# FiberOptic__3.net
KiCad netlist of a schematic drawn in Altium Designer
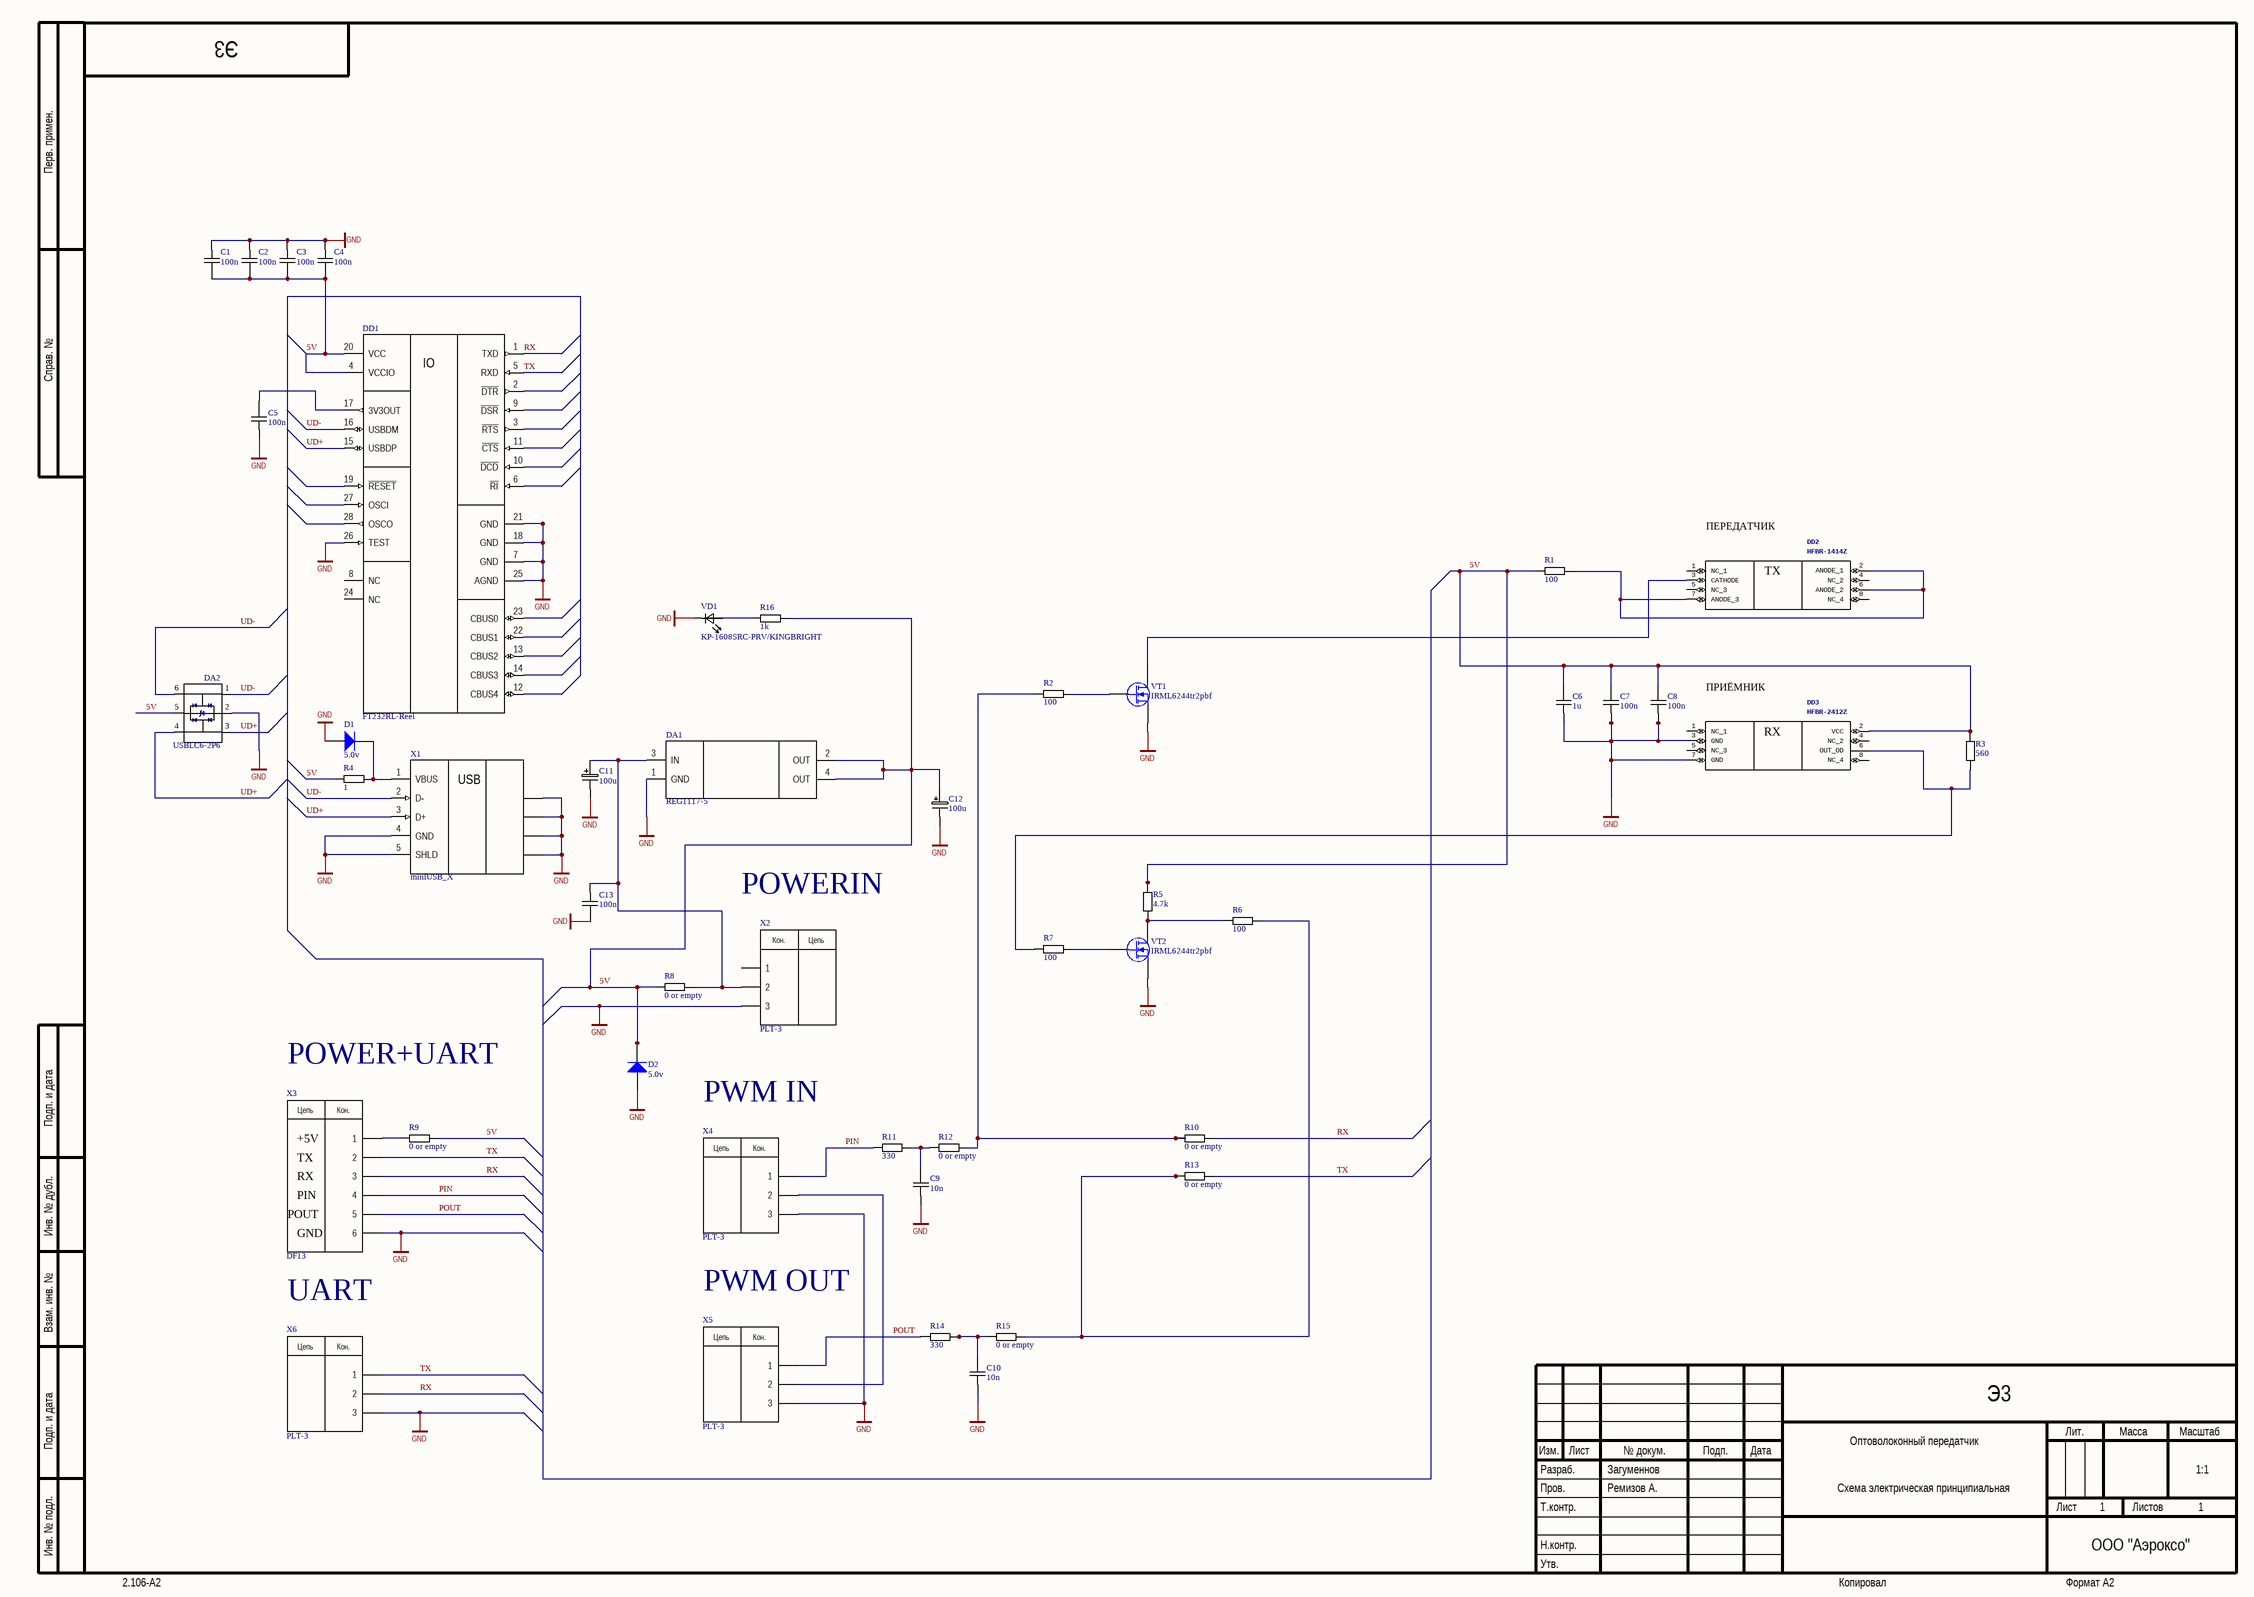
[diagram p0: FiberOptic_Э3.SchDoc]

(export (version "E")
  (design (tool "Eeschema 10.0.6"))
  (components
    (comp (ref "C1")
      (value "100n")
      (footprint "SMT0603CAP/VISHAY")
      (description "180p 50V 0603 cap")
      (libsource (lib "Логическая_Lib") (part "CC0603JRNPO9BN181/YAGEO"))
    )
    (comp (ref "C2")
      (value "100n")
      (footprint "SMT0603CAP/VISHAY")
      (description "180p 50V 0603 cap")
      (libsource (lib "Логическая_Lib") (part "CC0603JRNPO9BN181/YAGEO"))
    )
    (comp (ref "C3")
      (value "100n")
      (footprint "SMT0603CAP/VISHAY")
      (description "180p 50V 0603 cap")
      (libsource (lib "Логическая_Lib") (part "CC0603JRNPO9BN181/YAGEO"))
    )
    (comp (ref "C4")
      (value "100n")
      (footprint "SMT0603CAP/VISHAY")
      (description "180p 50V 0603 cap")
      (libsource (lib "Логическая_Lib") (part "CC0603JRNPO9BN181/YAGEO"))
    )
    (comp (ref "C5")
      (value "100n")
      (footprint "SMT0603CAP/VISHAY")
      (description "180p 50V 0603 cap")
      (libsource (lib "Логическая_Lib") (part "CC0603JRNPO9BN181/YAGEO"))
    )
    (comp (ref "C6")
      (value "1u")
      (footprint "SMT0603CAP/VISHAY")
      (description "180p 50V 0603 cap")
      (libsource (lib "Логическая_Lib") (part "CC0603JRNPO9BN181/YAGEO"))
    )
    (comp (ref "C7")
      (value "100n")
      (footprint "SMT0603CAP/VISHAY")
      (description "180p 50V 0603 cap")
      (libsource (lib "Логическая_Lib") (part "CC0603JRNPO9BN181/YAGEO"))
    )
    (comp (ref "C8")
      (value "100n")
      (footprint "SMT0603CAP/VISHAY")
      (description "180p 50V 0603 cap")
      (libsource (lib "Логическая_Lib") (part "CC0603JRNPO9BN181/YAGEO"))
    )
    (comp (ref "C9")
      (value "10n")
      (footprint "SMT0603CAP/VISHAY")
      (description "180p 50V 0603 cap")
      (libsource (lib "Логическая_Lib") (part "CC0603JRNPO9BN181/YAGEO"))
    )
    (comp (ref "C10")
      (value "10n")
      (footprint "SMT0603CAP/VISHAY")
      (description "180p 50V 0603 cap")
      (libsource (lib "Логическая_Lib") (part "CC0603JRNPO9BN181/YAGEO"))
    )
    (comp (ref "C11")
      (value "100u")
      (footprint "VISHAY-TANTALUM-CAP-TYPE-C/VISHAY")
      (description "100u 10V tantalum cap")
      (libsource (lib "FiberOptic_SCH") (part "293D107X9010C2TE3/VISHAY_1"))
    )
    (comp (ref "C12")
      (value "100u")
      (footprint "VISHAY-TANTALUM-CAP-TYPE-C/VISHAY")
      (description "100u 10V tantalum cap")
      (libsource (lib "FiberOptic_SCH") (part "293D107X9010C2TE3/VISHAY_1"))
    )
    (comp (ref "C13")
      (value "100n")
      (footprint "SMT0603CAP/VISHAY")
      (description "180p 50V 0603 cap")
      (libsource (lib "Логическая_Lib") (part "CC0603JRNPO9BN181/YAGEO"))
    )
    (comp (ref "D1")
      (value "5.0v")
      (footprint "SMB")
      (description "Default Diode")
      (fields (field (name "PUBLISHER") "Altium Limited"))
      (libsource (lib "Miscellaneous Devices") (part "Diode"))
    )
    (comp (ref "D2")
      (value "5.0v")
      (footprint "SMB")
      (description "Default Diode")
      (fields (field (name "PUBLISHER") "Altium Limited"))
      (libsource (lib "Miscellaneous Devices") (part "Diode"))
    )
    (comp (ref "DA1")
      (value "REG1117-5")
      (footprint "ZZ311")
      (description "800mA and 1A Low Dropout Positive Regulator 2.85V, 3.3V, 5V, and Adjustable")
      (fields (field (name "PUBLISHER") "Altium Limited"))
      (libsource (lib "FiberOptic_SCH") (part "REG1117-5"))
    )
    (comp (ref "DA2")
      (value "USBLC6-2P6")
      (footprint "SOT50P160X60-6N")
      (description "USBLC6 Series 2 Line 6 V SMT Bi Directional ESD Protection - SOT-666")
      (fields (field (name "MF") "STMicroelectronics"))
      (libsource (lib "FiberOptic_SCH") (part "USBLC6-2P6"))
    )
    (comp (ref "DD1")
      (value "FT232RL-Reel")
      (footprint "SSOP-28_N")
      (description "USB UART Asynchronous Serial Data Transfer Chip, 28-pin SSOP, Tape and Reel")
      (fields (field (name "MANUFACTURER") "FTDI"))
      (libsource (lib "БУГ2_Логическая_Lib") (part "FT232RL-Reel"))
    )
    (comp (ref "DD2")
      (value "HFBR-1414Z")
      (footprint "HFBR1414Z")
      (fields (field (name "RS_PART_NUMBER") "4965692"))
      (libsource (lib "FiberOptic_SCH") (part "HFBR-1414Z"))
    )
    (comp (ref "DD3")
      (value "HFBR-2412Z")
      (footprint "HFBR2412Z")
      (fields
        (field (name "MANUFACTURER_PART_NUMBER") "HFBR-1414Z")
        (field (name "RS_PART_NUMBER") "4965692")
      )
      (libsource (lib "FiberOptic_SCH") (part "HFBR-2412Z"))
    )
    (comp (ref "R1")
      (value "100")
      (footprint "SMT0603/VISHAY")
      (description "10k")
      (libsource (lib "FiberOptic_SCH") (part "CRCW060310K0FKEA/MURATA"))
    )
    (comp (ref "R2")
      (value "100")
      (footprint "SMT0603/VISHAY")
      (description "10k")
      (libsource (lib "FiberOptic_SCH") (part "CRCW060310K0FKEA/MURATA"))
    )
    (comp (ref "R3")
      (value "560")
      (footprint "SMT0603/VISHAY")
      (description "10k")
      (libsource (lib "FiberOptic_SCH") (part "CRCW060310K0FKEA/MURATA"))
    )
    (comp (ref "R4")
      (value "1")
      (footprint "SMT0603/VISHAY")
      (description "0")
      (libsource (lib "БУГ_Lib") (part "CRCW060310K0FKEA/MURATA"))
    )
    (comp (ref "R5")
      (value "4.7k")
      (footprint "SMT0603/VISHAY")
      (description "10k")
      (libsource (lib "FiberOptic_SCH") (part "CRCW060310K0FKEA/MURATA"))
    )
    (comp (ref "R6")
      (value "100")
      (footprint "SMT0603/VISHAY")
      (description "10k")
      (libsource (lib "FiberOptic_SCH") (part "CRCW060310K0FKEA/MURATA"))
    )
    (comp (ref "R7")
      (value "100")
      (footprint "SMT0603/VISHAY")
      (description "10k")
      (libsource (lib "FiberOptic_SCH") (part "CRCW060310K0FKEA/MURATA"))
    )
    (comp (ref "R8")
      (value "0 or empty")
      (footprint "SMT0603/VISHAY")
      (libsource (lib "FiberOptic_SCH") (part "CRCW060310K0FKEA/MURATA"))
    )
    (comp (ref "R9")
      (value "0 or empty")
      (footprint "SMT0603/VISHAY")
      (libsource (lib "FiberOptic_SCH") (part "CRCW060310K0FKEA/MURATA"))
    )
    (comp (ref "R10")
      (value "0 or empty")
      (footprint "SMT0603/VISHAY")
      (description "10k")
      (libsource (lib "FiberOptic_SCH") (part "CRCW060310K0FKEA/MURATA"))
    )
    (comp (ref "R11")
      (value "330")
      (footprint "SMT0603/VISHAY")
      (description "0 or empty")
      (libsource (lib "FiberOptic_SCH") (part "CRCW060310K0FKEA/MURATA"))
    )
    (comp (ref "R12")
      (value "0 or empty")
      (footprint "SMT0603/VISHAY")
      (libsource (lib "FiberOptic_SCH") (part "CRCW060310K0FKEA/MURATA"))
    )
    (comp (ref "R13")
      (value "0 or empty")
      (footprint "SMT0603/VISHAY")
      (description "10k")
      (libsource (lib "FiberOptic_SCH") (part "CRCW060310K0FKEA/MURATA"))
    )
    (comp (ref "R14")
      (value "330")
      (footprint "SMT0603/VISHAY")
      (description "10k")
      (libsource (lib "FiberOptic_SCH") (part "CRCW060310K0FKEA/MURATA"))
    )
    (comp (ref "R15")
      (value "0 or empty")
      (footprint "SMT0603/VISHAY")
      (description "10k")
      (libsource (lib "FiberOptic_SCH") (part "CRCW060310K0FKEA/MURATA"))
    )
    (comp (ref "R16")
      (value "1k")
      (footprint "SMT0603/VISHAY")
      (description "10k")
      (libsource (lib "Логическая_Lib") (part "CRCW060310K0FKEA/MURATA"))
    )
    (comp (ref "VD1")
      (value "KP-1608SRC-PRV/KINGBRIGHT")
      (footprint "1.6x0.8SMTLED/KINGBRIGHT")
      (description "Red 0603 LED")
      (libsource (lib "Логическая_Lib") (part "KP-1608SRC-PRV/KINGBRIGHT"))
    )
    (comp (ref "VT1")
      (value "IRML6244tr2pbf")
      (footprint "SOT23_N")
      (description "N-Channel MOSFET")
      (fields (field (name "PUBLISHER") "Altium Limited"))
      (libsource (lib "FiberOptic_SCH") (part "IRML6244tr2pbf"))
    )
    (comp (ref "VT2")
      (value "IRML6244tr2pbf")
      (footprint "SOT23_N")
      (description "N-Channel MOSFET")
      (fields (field (name "PUBLISHER") "Altium Limited"))
      (libsource (lib "FiberOptic_SCH") (part "IRML6244tr2pbf"))
    )
    (comp (ref "X1")
      (value "miniUSB_X")
      (footprint "miniUSB_AB")
      (description "USB 2.0, Right Angle, SMT, A Type, Receptacle, 5 Position, Black")
      (fields (field (name "PUBLISHER") "Altium Limited"))
      (libsource (lib "БУГ2_Логическая_Lib") (part "miniUSB_X"))
    )
    (comp (ref "X2") (value "PLT-3") (footprint "PLT-3T") (libsource (lib "") (part "PLT-3_1")))
    (comp (ref "X3")
      (value "DF13")
      (footprint "HIROSE DF13-6P-1.25H")
      (libsource (lib "FiberOptic_SCH") (part "DF13-6P"))
    )
    (comp (ref "X4") (value "PLT-3") (footprint "PLT-3T") (libsource (lib "FiberOptic_SCH") (part "PLT-3")))
    (comp (ref "X5") (value "PLT-3") (footprint "PLT-3T") (libsource (lib "FiberOptic_SCH") (part "PLT-3")))
    (comp (ref "X6") (value "PLT-3") (footprint "PLT-3T") (libsource (lib "FiberOptic_SCH") (part "PLT-3")))
  )
  (nets
    (net (code "1") (name "/5V") (class "Default")
      (node (ref "C1") (pin "1") (pinfunction "1_1") (pintype "passive"))
      (node (ref "C12") (pin "1") (pinfunction "1_1") (pintype "passive"))
      (node (ref "C2") (pin "1") (pinfunction "1_1") (pintype "passive"))
      (node (ref "C3") (pin "1") (pinfunction "1_1") (pintype "passive"))
      (node (ref "C4") (pin "1") (pinfunction "1_1") (pintype "passive"))
      (node (ref "C6") (pin "1") (pinfunction "1_1") (pintype "passive"))
      (node (ref "C7") (pin "1") (pinfunction "1_1") (pintype "passive"))
      (node (ref "C8") (pin "1") (pinfunction "1_1") (pintype "passive"))
      (node (ref "D2") (pin "2") (pinfunction "K_2") (pintype "passive"))
      (node (ref "DA1") (pin "2") (pinfunction "OUT_2") (pintype "power_in"))
      (node (ref "DA1") (pin "4") (pinfunction "OUT_4") (pintype "power_in"))
      (node (ref "DA2") (pin "5") (pinfunction "VBUS_5") (pintype "power_in"))
      (node (ref "DD1") (pin "20") (pinfunction "VCC_20") (pintype "power_in"))
      (node (ref "DD1") (pin "4") (pinfunction "VCCIO_4") (pintype "power_in"))
      (node (ref "DD3") (pin "2") (pinfunction "VCC_2") (pintype "bidirectional"))
      (node (ref "R1") (pin "2") (pinfunction "2_2") (pintype "passive"))
      (node (ref "R16") (pin "2") (pinfunction "2_2") (pintype "passive"))
      (node (ref "R3") (pin "2") (pinfunction "2_2") (pintype "passive"))
      (node (ref "R4") (pin "2") (pinfunction "2_2") (pintype "passive"))
      (node (ref "R5") (pin "1") (pinfunction "1_1") (pintype "passive"))
      (node (ref "R8") (pin "1") (pinfunction "1_1") (pintype "passive"))
      (node (ref "R9") (pin "2") (pinfunction "2_2") (pintype "passive"))
    )
    (net (code "2") (name "/PIN") (class "Default")
      (node (ref "R11") (pin "1") (pinfunction "1_1") (pintype "passive"))
      (node (ref "X3") (pin "4") (pinfunction "4_4") (pintype "passive"))
      (node (ref "X4") (pin "1") (pinfunction "1_1") (pintype "passive"))
    )
    (net (code "3") (name "/POUT") (class "Default")
      (node (ref "R14") (pin "1") (pinfunction "1_1") (pintype "passive"))
      (node (ref "X3") (pin "5") (pinfunction "5_5") (pintype "passive"))
      (node (ref "X5") (pin "1") (pinfunction "1_1") (pintype "passive"))
    )
    (net (code "4") (name "/RX") (class "Default")
      (node (ref "DD1") (pin "1") (pinfunction "TXD_1") (pintype "output"))
      (node (ref "R10") (pin "2") (pinfunction "2_2") (pintype "passive"))
      (node (ref "X3") (pin "3") (pinfunction "3_3") (pintype "passive"))
      (node (ref "X6") (pin "2") (pinfunction "2_2") (pintype "passive"))
    )
    (net (code "5") (name "/TX") (class "Default")
      (node (ref "DD1") (pin "5") (pinfunction "RXD_5") (pintype "input"))
      (node (ref "R13") (pin "2") (pinfunction "2_2") (pintype "passive"))
      (node (ref "X3") (pin "2") (pinfunction "2_2") (pintype "passive"))
      (node (ref "X6") (pin "1") (pinfunction "1_1") (pintype "passive"))
    )
    (net (code "6") (name "/UD+") (class "Default")
      (node (ref "DA2") (pin "3") (pinfunction "I/O2_1_3") (pintype "bidirectional"))
      (node (ref "DA2") (pin "4") (pinfunction "I/O2_2_4") (pintype "bidirectional"))
      (node (ref "DD1") (pin "15") (pinfunction "USBDP_15") (pintype "bidirectional"))
      (node (ref "X1") (pin "3") (pinfunction "D+_3") (pintype "input"))
    )
    (net (code "7") (name "/UD-") (class "Default")
      (node (ref "DA2") (pin "1") (pinfunction "I/O1_1_1") (pintype "bidirectional"))
      (node (ref "DA2") (pin "6") (pinfunction "I/O1_2_6") (pintype "bidirectional"))
      (node (ref "DD1") (pin "16") (pinfunction "USBDM_16") (pintype "bidirectional"))
      (node (ref "X1") (pin "2") (pinfunction "D-_2") (pintype "input"))
    )
    (net (code "8") (name "GND") (class "Default")
      (node (ref "C1") (pin "2") (pinfunction "2_2") (pintype "passive"))
      (node (ref "C10") (pin "2") (pinfunction "2_2") (pintype "passive"))
      (node (ref "C11") (pin "2") (pinfunction "2_2") (pintype "passive"))
      (node (ref "C12") (pin "2") (pinfunction "2_2") (pintype "passive"))
      (node (ref "C13") (pin "1") (pinfunction "1_1") (pintype "passive"))
      (node (ref "C2") (pin "2") (pinfunction "2_2") (pintype "passive"))
      (node (ref "C3") (pin "2") (pinfunction "2_2") (pintype "passive"))
      (node (ref "C4") (pin "2") (pinfunction "2_2") (pintype "passive"))
      (node (ref "C5") (pin "2") (pinfunction "2_2") (pintype "passive"))
      (node (ref "C6") (pin "2") (pinfunction "2_2") (pintype "passive"))
      (node (ref "C7") (pin "2") (pinfunction "2_2") (pintype "passive"))
      (node (ref "C8") (pin "2") (pinfunction "2_2") (pintype "passive"))
      (node (ref "C9") (pin "2") (pinfunction "2_2") (pintype "passive"))
      (node (ref "D1") (pin "1") (pinfunction "A_1") (pintype "passive"))
      (node (ref "D2") (pin "1") (pinfunction "A_1") (pintype "passive"))
      (node (ref "DA1") (pin "1") (pinfunction "GND_1") (pintype "power_in"))
      (node (ref "DA2") (pin "2") (pinfunction "GND_2") (pintype "power_in"))
      (node (ref "DD1") (pin "18") (pinfunction "GND_18") (pintype "power_in"))
      (node (ref "DD1") (pin "21") (pinfunction "GND_21") (pintype "power_in"))
      (node (ref "DD1") (pin "25") (pinfunction "AGND_25") (pintype "power_in"))
      (node (ref "DD1") (pin "26") (pinfunction "TEST_26") (pintype "input"))
      (node (ref "DD1") (pin "7") (pinfunction "GND_7") (pintype "power_in"))
      (node (ref "DD3") (pin "3") (pinfunction "GND_3") (pintype "bidirectional"))
      (node (ref "DD3") (pin "7") (pinfunction "GND_7") (pintype "bidirectional"))
      (node (ref "VD1") (pin "2") (pinfunction "2_2") (pintype "passive"))
      (node (ref "VT1") (pin "3") (pinfunction "S_3") (pintype "passive"))
      (node (ref "VT2") (pin "3") (pinfunction "S_3") (pintype "passive"))
      (node (ref "X1") (pin "4") (pinfunction "GND_4") (pintype "power_in"))
      (node (ref "X1") (pin "5") (pinfunction "SHLD_5") (pintype "passive"))
      (node (ref "X1") (pin "6") (pinfunction "SHLD_6") (pintype "passive"))
      (node (ref "X1") (pin "7") (pinfunction "SHLD_7") (pintype "passive"))
      (node (ref "X1") (pin "8") (pinfunction "SHLD_8") (pintype "passive"))
      (node (ref "X1") (pin "9") (pinfunction "SHLD_9") (pintype "passive"))
      (node (ref "X2") (pin "3") (pinfunction "3_3") (pintype "passive"))
      (node (ref "X3") (pin "6") (pinfunction "6_6") (pintype "passive"))
      (node (ref "X4") (pin "3") (pinfunction "3_3") (pintype "passive"))
      (node (ref "X5") (pin "3") (pinfunction "3_3") (pintype "passive"))
      (node (ref "X6") (pin "3") (pinfunction "3_3") (pintype "passive"))
    )
    (net (code "9") (name "Net-(C9-Pad1)") (class "Default")
      (node (ref "C9") (pin "1") (pinfunction "1_1") (pintype "passive"))
      (node (ref "R11") (pin "2") (pinfunction "2_2") (pintype "passive"))
      (node (ref "R12") (pin "1") (pinfunction "1_1") (pintype "passive"))
    )
    (net (code "10") (name "Net-(C10-Pad1)") (class "Default")
      (node (ref "C10") (pin "1") (pinfunction "1_1") (pintype "passive"))
      (node (ref "R14") (pin "2") (pinfunction "2_2") (pintype "passive"))
      (node (ref "R15") (pin "1") (pinfunction "1_1") (pintype "passive"))
    )
    (net (code "11") (name "Net-(D1-K)") (class "Default")
      (node (ref "D1") (pin "2") (pinfunction "K_2") (pintype "passive"))
      (node (ref "R4") (pin "1") (pinfunction "1_1") (pintype "passive"))
      (node (ref "X1") (pin "1") (pinfunction "VBUS_1") (pintype "power_in"))
    )
    (net (code "12") (name "Net-(DA1-IN)") (class "Default")
      (node (ref "C11") (pin "1") (pinfunction "1_1") (pintype "passive"))
      (node (ref "C13") (pin "2") (pinfunction "2_2") (pintype "passive"))
      (node (ref "DA1") (pin "3") (pinfunction "IN_3") (pintype "power_in"))
      (node (ref "R8") (pin "2") (pinfunction "2_2") (pintype "passive"))
      (node (ref "X2") (pin "2") (pinfunction "2_2") (pintype "passive"))
    )
    (net (code "13") (name "Net-(DD1-3V3OUT)") (class "Default")
      (node (ref "C5") (pin "1") (pinfunction "1_1") (pintype "passive"))
      (node (ref "DD1") (pin "17") (pinfunction "3V3OUT_17") (pintype "output"))
    )
    (net (code "14") (name "Net-(DD2-ANODE_1)") (class "Default")
      (node (ref "DD2") (pin "2") (pinfunction "ANODE_1_2") (pintype "bidirectional"))
      (node (ref "DD2") (pin "6") (pinfunction "ANODE_2_6") (pintype "bidirectional"))
      (node (ref "DD2") (pin "7") (pinfunction "ANODE_3_7") (pintype "bidirectional"))
      (node (ref "R1") (pin "1") (pinfunction "1_1") (pintype "passive"))
    )
    (net (code "15") (name "Net-(DD2-CATHODE)") (class "Default")
      (node (ref "DD2") (pin "3") (pinfunction "CATHODE_3") (pintype "bidirectional"))
      (node (ref "VT1") (pin "1") (pinfunction "D_1") (pintype "passive"))
    )
    (net (code "16") (name "Net-(DD3-OUT_OD)") (class "Default")
      (node (ref "DD3") (pin "6") (pinfunction "OUT_OD_6") (pintype "open_collector"))
      (node (ref "R3") (pin "1") (pinfunction "1_1") (pintype "passive"))
      (node (ref "R7") (pin "2") (pinfunction "2_2") (pintype "passive"))
    )
    (net (code "17") (name "Net-(R9-Pad1)") (class "Default")
      (node (ref "R9") (pin "1") (pinfunction "1_1") (pintype "passive"))
      (node (ref "X3") (pin "1") (pinfunction "1_1") (pintype "passive"))
    )
    (net (code "18") (name "Net-(R10-Pad1)") (class "Default")
      (node (ref "R10") (pin "1") (pinfunction "1_1") (pintype "passive"))
      (node (ref "R12") (pin "2") (pinfunction "2_2") (pintype "passive"))
      (node (ref "R2") (pin "2") (pinfunction "2_2") (pintype "passive"))
    )
    (net (code "19") (name "Net-(R13-Pad1)") (class "Default")
      (node (ref "R13") (pin "1") (pinfunction "1_1") (pintype "passive"))
      (node (ref "R15") (pin "2") (pinfunction "2_2") (pintype "passive"))
      (node (ref "R6") (pin "1") (pinfunction "1_1") (pintype "passive"))
    )
    (net (code "20") (name "Net-(R16-Pad1)") (class "Default")
      (node (ref "R16") (pin "1") (pinfunction "1_1") (pintype "passive"))
      (node (ref "VD1") (pin "1") (pinfunction "1_1") (pintype "passive"))
    )
    (net (code "21") (name "Net-(VT1-G)") (class "Default")
      (node (ref "R2") (pin "1") (pinfunction "1_1") (pintype "passive"))
      (node (ref "VT1") (pin "2") (pinfunction "G_2") (pintype "passive"))
    )
    (net (code "22") (name "Net-(VT2-D)") (class "Default")
      (node (ref "R5") (pin "2") (pinfunction "2_2") (pintype "passive"))
      (node (ref "R6") (pin "2") (pinfunction "2_2") (pintype "passive"))
      (node (ref "VT2") (pin "1") (pinfunction "D_1") (pintype "passive"))
    )
    (net (code "23") (name "Net-(VT2-G)") (class "Default")
      (node (ref "R7") (pin "1") (pinfunction "1_1") (pintype "passive"))
      (node (ref "VT2") (pin "2") (pinfunction "G_2") (pintype "passive"))
    )
    (net (code "24") (name "Net-(X4-Pad2)") (class "Default")
      (node (ref "X4") (pin "2") (pinfunction "2_2") (pintype "passive"))
      (node (ref "X5") (pin "2") (pinfunction "2_2") (pintype "passive"))
    )
    (net (code "25") (name "unconnected-(DD1-CBUS0-Pad23)") (class "Default")
      (node (ref "DD1") (pin "23") (pinfunction "CBUS0_23") (pintype "bidirectional"))
    )
    (net (code "26") (name "unconnected-(DD1-CBUS1-Pad22)") (class "Default")
      (node (ref "DD1") (pin "22") (pinfunction "CBUS1_22") (pintype "bidirectional"))
    )
    (net (code "27") (name "unconnected-(DD1-CBUS2-Pad13)") (class "Default")
      (node (ref "DD1") (pin "13") (pinfunction "CBUS2_13") (pintype "bidirectional"))
    )
    (net (code "28") (name "unconnected-(DD1-CBUS3-Pad14)") (class "Default")
      (node (ref "DD1") (pin "14") (pinfunction "CBUS3_14") (pintype "bidirectional"))
    )
    (net (code "29") (name "unconnected-(DD1-CBUS4-Pad12)") (class "Default")
      (node (ref "DD1") (pin "12") (pinfunction "CBUS4_12") (pintype "bidirectional"))
    )
    (net (code "30") (name "unconnected-(DD1-NC-Pad8)") (class "Default")
      (node (ref "DD1") (pin "8") (pinfunction "NC_8") (pintype "passive"))
    )
    (net (code "31") (name "unconnected-(DD1-NC-Pad24)") (class "Default")
      (node (ref "DD1") (pin "24") (pinfunction "NC_24") (pintype "passive"))
    )
    (net (code "32") (name "unconnected-(DD1-OSCI-Pad27)") (class "Default")
      (node (ref "DD1") (pin "27") (pinfunction "OSCI_27") (pintype "input"))
    )
    (net (code "33") (name "unconnected-(DD1-OSCO-Pad28)") (class "Default")
      (node (ref "DD1") (pin "28") (pinfunction "OSCO_28") (pintype "output"))
    )
    (net (code "34") (name "unconnected-(DD1-~{CTS}-Pad11)") (class "Default")
      (node (ref "DD1") (pin "11") (pinfunction "~{CTS}_11") (pintype "input"))
    )
    (net (code "35") (name "unconnected-(DD1-~{DCD}-Pad10)") (class "Default")
      (node (ref "DD1") (pin "10") (pinfunction "~{DCD}_10") (pintype "input"))
    )
    (net (code "36") (name "unconnected-(DD1-~{DSR}-Pad9)") (class "Default")
      (node (ref "DD1") (pin "9") (pinfunction "~{DSR}_9") (pintype "input"))
    )
    (net (code "37") (name "unconnected-(DD1-~{DTR}-Pad2)") (class "Default")
      (node (ref "DD1") (pin "2") (pinfunction "~{DTR}_2") (pintype "output"))
    )
    (net (code "38") (name "unconnected-(DD1-~{RESET}-Pad19)") (class "Default")
      (node (ref "DD1") (pin "19") (pinfunction "~{RESET}_19") (pintype "input"))
    )
    (net (code "39") (name "unconnected-(DD1-~{RI}-Pad6)") (class "Default")
      (node (ref "DD1") (pin "6") (pinfunction "~{RI}_6") (pintype "input"))
    )
    (net (code "40") (name "unconnected-(DD1-~{RTS}-Pad3)") (class "Default")
      (node (ref "DD1") (pin "3") (pinfunction "~{RTS}_3") (pintype "output"))
    )
    (net (code "41") (name "unconnected-(DD2-NC_1-Pad1)") (class "Default")
      (node (ref "DD2") (pin "1") (pinfunction "NC_1_1") (pintype "bidirectional"))
    )
    (net (code "42") (name "unconnected-(DD2-NC_2-Pad4)") (class "Default")
      (node (ref "DD2") (pin "4") (pinfunction "NC_2_4") (pintype "bidirectional"))
    )
    (net (code "43") (name "unconnected-(DD2-NC_3-Pad5)") (class "Default")
      (node (ref "DD2") (pin "5") (pinfunction "NC_3_5") (pintype "bidirectional"))
    )
    (net (code "44") (name "unconnected-(DD2-NC_4-Pad8)") (class "Default")
      (node (ref "DD2") (pin "8") (pinfunction "NC_4_8") (pintype "bidirectional"))
    )
    (net (code "45") (name "unconnected-(DD3-NC_1-Pad1)") (class "Default")
      (node (ref "DD3") (pin "1") (pinfunction "NC_1_1") (pintype "bidirectional"))
    )
    (net (code "46") (name "unconnected-(DD3-NC_2-Pad4)") (class "Default")
      (node (ref "DD3") (pin "4") (pinfunction "NC_2_4") (pintype "bidirectional"))
    )
    (net (code "47") (name "unconnected-(DD3-NC_3-Pad5)") (class "Default")
      (node (ref "DD3") (pin "5") (pinfunction "NC_3_5") (pintype "bidirectional"))
    )
    (net (code "48") (name "unconnected-(DD3-NC_4-Pad8)") (class "Default")
      (node (ref "DD3") (pin "8") (pinfunction "NC_4_8") (pintype "bidirectional"))
    )
    (net (code "49") (name "unconnected-(X2-Pad1)") (class "Default")
      (node (ref "X2") (pin "1") (pinfunction "1_1") (pintype "passive"))
    )
  )
)
